# Patient_Protection.net
KiCad netlist of a schematic drawn in Altium Designer
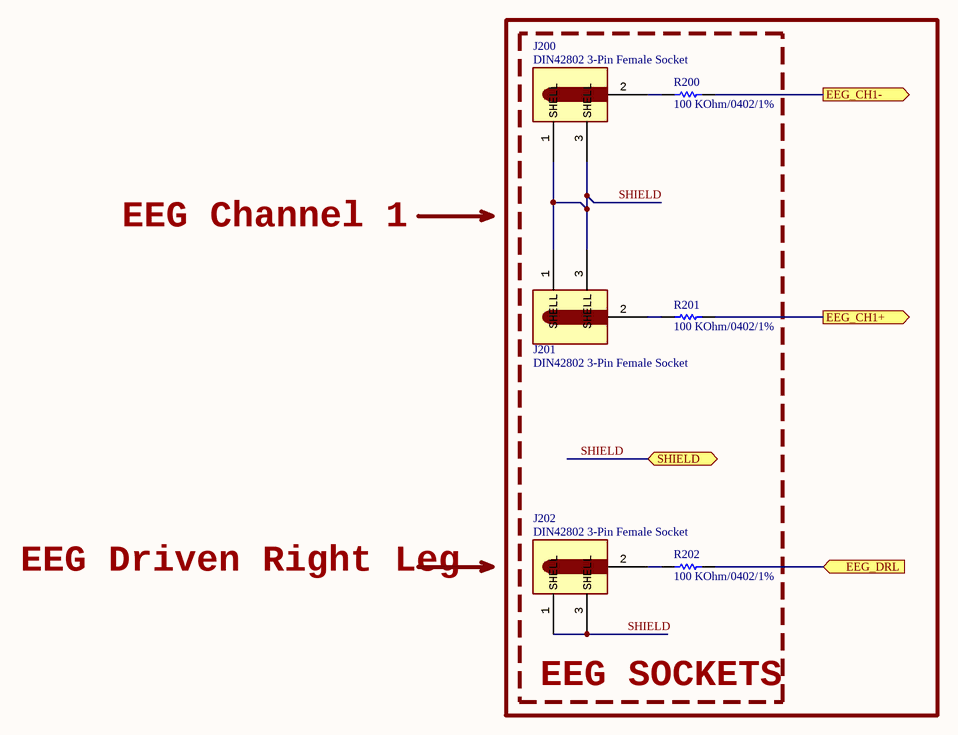
[diagram p0: Patient Protection.SchDoc]

(export (version "E")
  (design (tool "Eeschema 10.0.6"))
  (components
    (comp (ref "J200")
      (value "DIN42802 3-Pin Female Socket")
      (footprint "DIN42802-1.5MM SOCKET")
      (description "3 PIN Socket Female Socket for PCB EEG EMG DIN42802 1.5 mm Connector")
      (fields (field (name "Comment") "DIN42802 1.5mm"))
      (libsource (lib "Giang's Libs") (part "DIN42802 1.5mm"))
    )
    (comp (ref "J201")
      (value "DIN42802 3-Pin Female Socket")
      (footprint "DIN42802-1.5MM SOCKET")
      (description "3 PIN Socket Female Socket for PCB EEG EMG DIN42802 1.5 mm Connector")
      (fields (field (name "Comment") "DIN42802 1.5mm"))
      (libsource (lib "") (part "DIN42802 1.5mm_1"))
    )
    (comp (ref "J202")
      (value "DIN42802 3-Pin Female Socket")
      (footprint "DIN42802-1.5MM SOCKET")
      (description "3 PIN Socket Female Socket for PCB EEG EMG DIN42802 1.5 mm Connector")
      (fields (field (name "Comment") "DIN42802 1.5mm"))
      (libsource (lib "Giang's Libs") (part "DIN42802 1.5mm"))
    )
    (comp (ref "R200")
      (value "100 KOhm/0402/1%")
      (footprint "R0402")
      (description "Code 104, 1/16W 1%")
      (fields (field (name "Comment") "Resistor 100 KOhm 0402 1%"))
      (libsource (lib "Giang_Resistor") (part "Resistor 100 KOhm 0402 1%"))
    )
    (comp (ref "R201")
      (value "100 KOhm/0402/1%")
      (footprint "R0402")
      (description "Code 104, 1/16W 1%")
      (fields (field (name "Comment") "Resistor 100 KOhm 0402 1%"))
      (libsource (lib "Giang_Resistor") (part "Resistor 100 KOhm 0402 1%"))
    )
    (comp (ref "R202")
      (value "100 KOhm/0402/1%")
      (footprint "R0402")
      (description "Code 104, 1/16W 1%")
      (fields (field (name "Comment") "Resistor 100 KOhm 0402 1%"))
      (libsource (lib "Giang_Resistor") (part "Resistor 100 KOhm 0402 1%"))
    )
  )
  (nets
    (net (code "1") (name "/EEG_CH1+") (class "Default")
      (node (ref "R201") (pin "2") (pinfunction "2_2") (pintype "passive"))
    )
    (net (code "2") (name "/EEG_CH1-") (class "Default")
      (node (ref "R200") (pin "2") (pinfunction "2_2") (pintype "passive"))
    )
    (net (code "3") (name "/EEG_DRL") (class "Default")
      (node (ref "R202") (pin "2") (pinfunction "2_2") (pintype "passive"))
    )
    (net (code "4") (name "/SHIELD") (class "Default")
      (node (ref "J200") (pin "1") (pinfunction "SHELL_1") (pintype "passive"))
      (node (ref "J200") (pin "3") (pinfunction "SHELL_3") (pintype "passive"))
      (node (ref "J201") (pin "1") (pinfunction "SHELL_1") (pintype "passive"))
      (node (ref "J201") (pin "3") (pinfunction "SHELL_3") (pintype "passive"))
      (node (ref "J202") (pin "1") (pinfunction "SHELL_1") (pintype "passive"))
      (node (ref "J202") (pin "3") (pinfunction "SHELL_3") (pintype "passive"))
    )
    (net (code "5") (name "Net-(J200-PORT)") (class "Default")
      (node (ref "J200") (pin "2") (pinfunction "PORT_2") (pintype "passive"))
      (node (ref "R200") (pin "1") (pinfunction "1_1") (pintype "passive"))
    )
    (net (code "6") (name "Net-(J201-PORT)") (class "Default")
      (node (ref "J201") (pin "2") (pinfunction "PORT_2") (pintype "passive"))
      (node (ref "R201") (pin "1") (pinfunction "1_1") (pintype "passive"))
    )
    (net (code "7") (name "Net-(J202-PORT)") (class "Default")
      (node (ref "J202") (pin "2") (pinfunction "PORT_2") (pintype "passive"))
      (node (ref "R202") (pin "1") (pinfunction "1_1") (pintype "passive"))
    )
  )
)
